# MainPower.net
KiCad netlist of a schematic drawn in Altium Designer
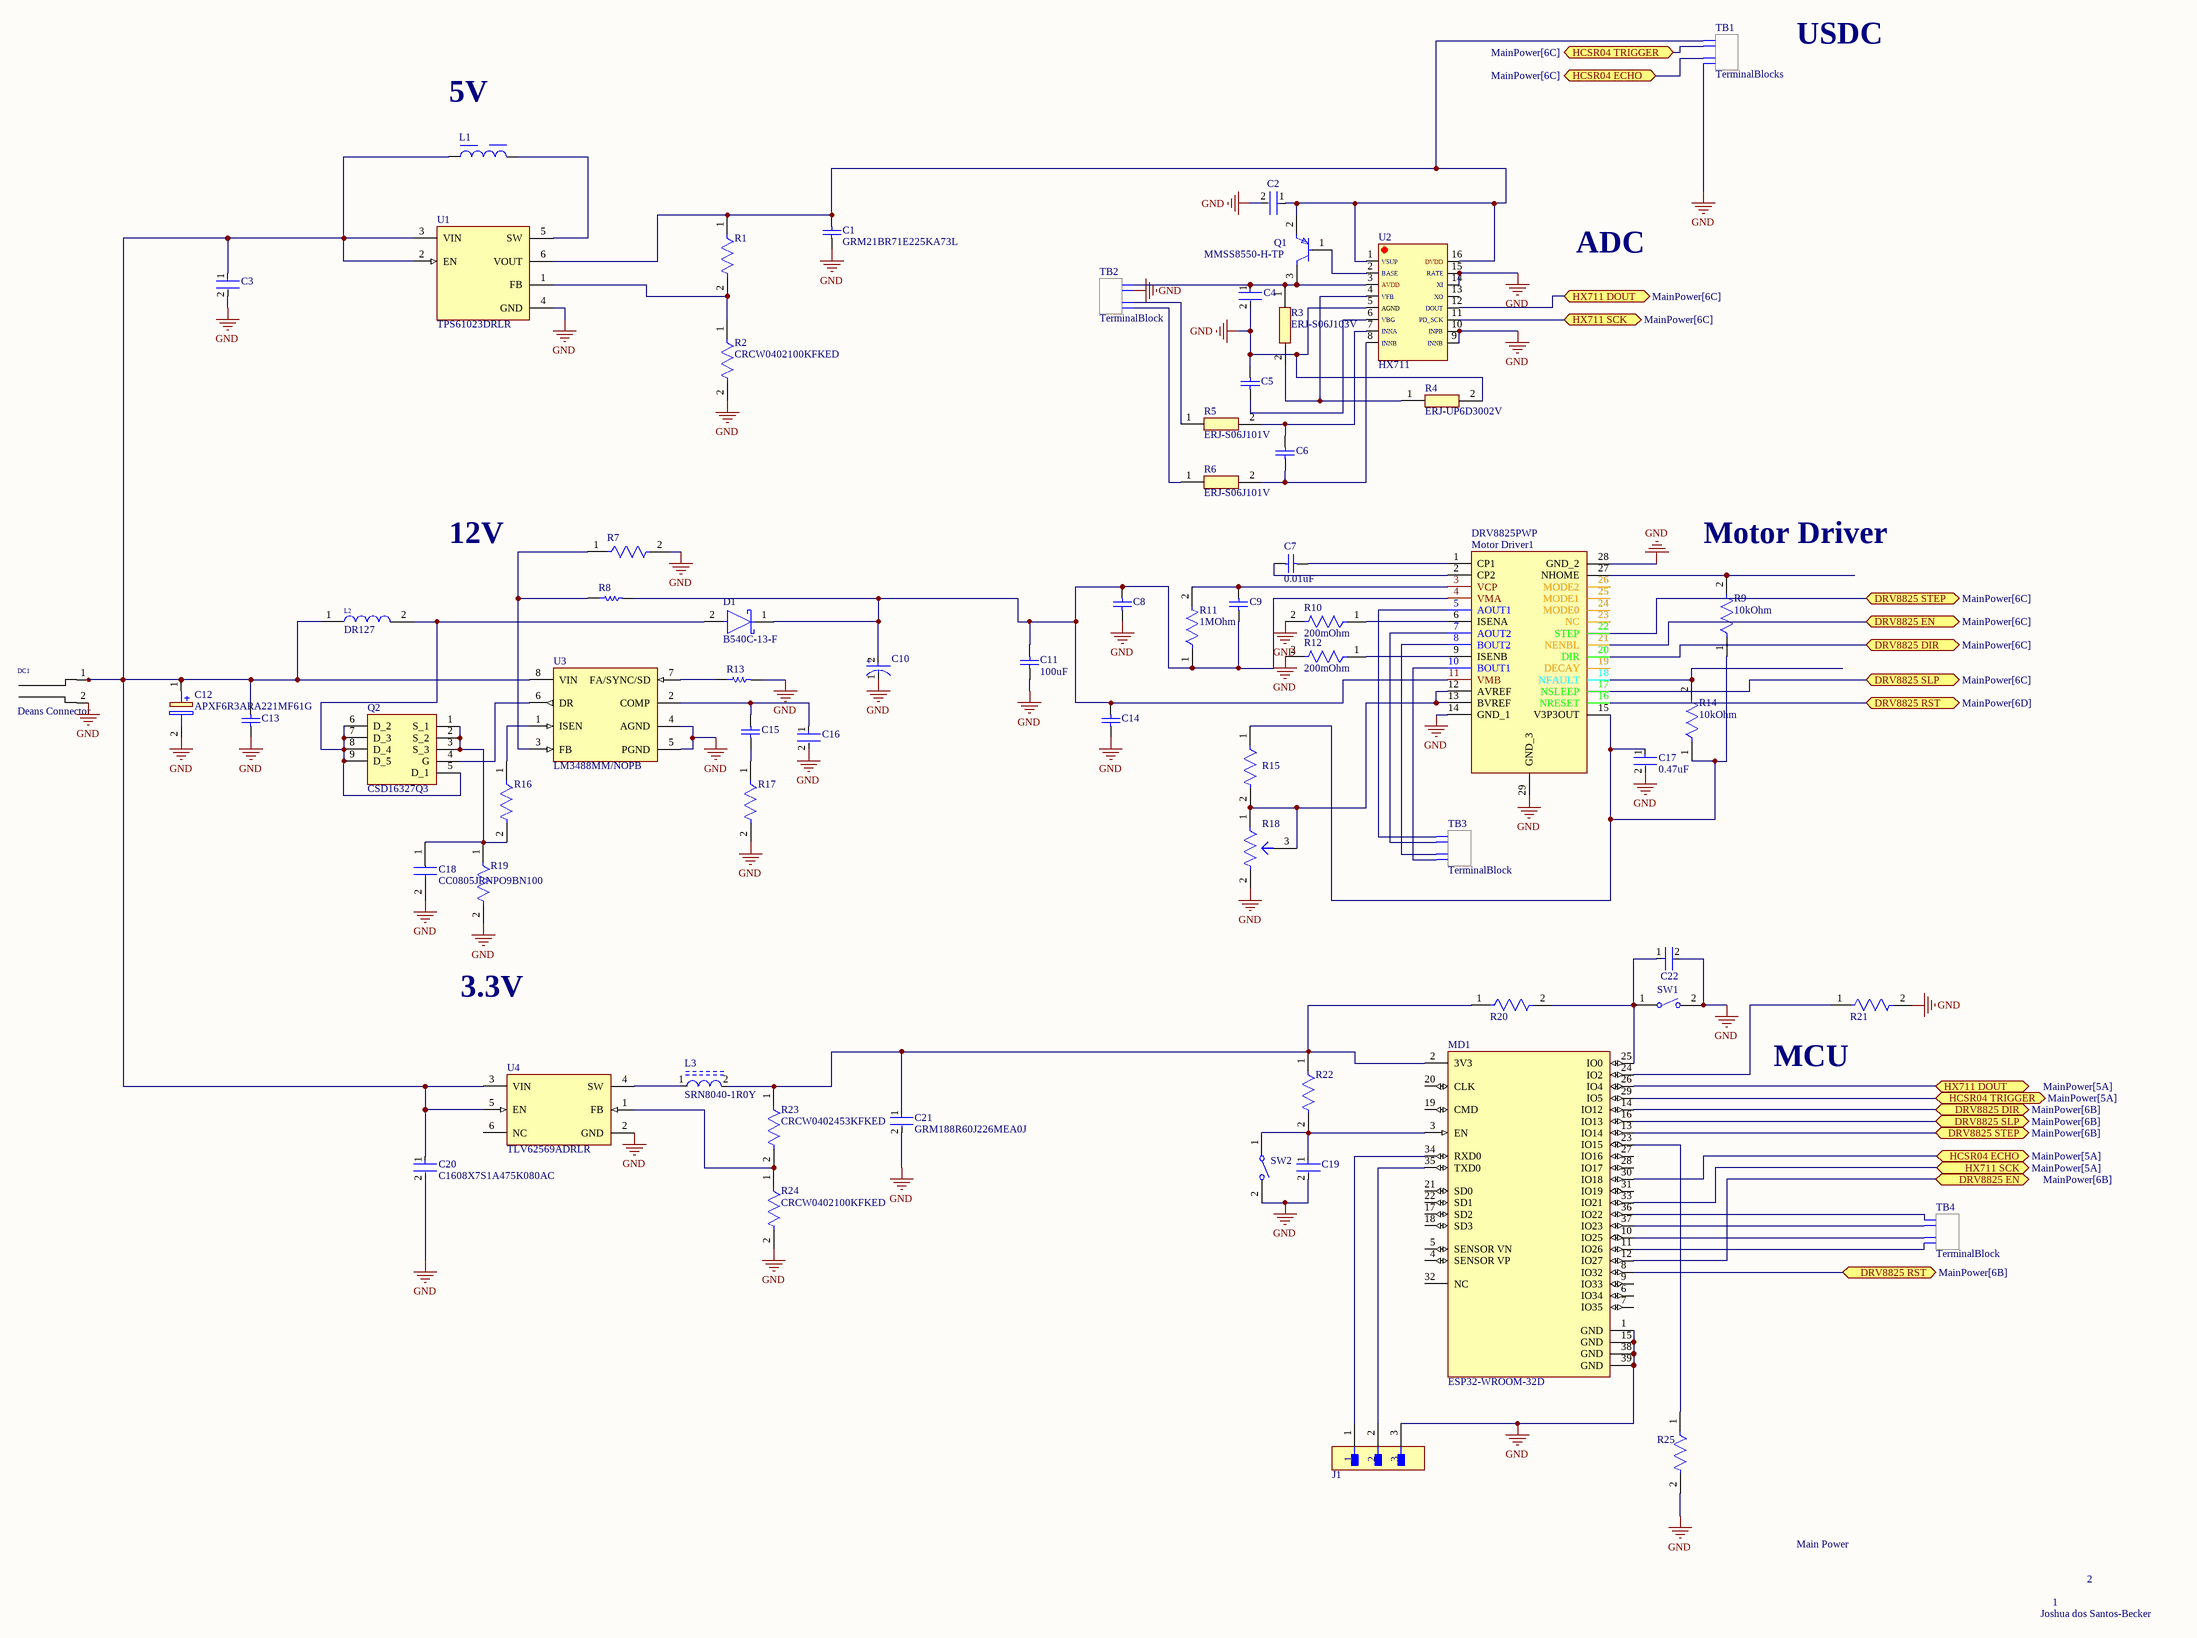
[diagram p0: MainPower.SchDoc]

(export (version "E")
  (design (tool "Eeschema 10.0.6"))
  (components
    (comp (ref "C1")
      (value "GRM21BR71E225KA73L")
      (footprint "CAPC2013X140X45NL15T25")
      (fields (field (name "MANUFACTURER") "Murata"))
      (libsource (lib "Altium Content Vault") (part "CAP"))
    )
    (comp (ref "C2")
      (value "GRM21BR61C106KE15L")
      (footprint "FP-GRM21B-0_1-IPC_C")
      (description "Chip Multilayer Ceramic Capacitors for General Purpose, 0805, 10uF, X5R, 15%, 10%, 16V")
      (fields (field (name "TOLERANCE") "10%") (field (name "VOLTAGE") "16V"))
      (libsource (lib "Altium Content Vault") (part "b4654b650e69147ec39a6b967a45e02"))
    )
    (comp (ref "C3")
      (value "C0805C106K8PACTU")
      (footprint "FP-C0805C-DG-MFG")
      (description "CAP CER 10UF 10V X5R 0805")
      (fields (field (name "TOLERANCE") "10%") (field (name "MANUFACTURER") "Kemet"))
      (libsource (lib "Altium Content Vault") (part "11868f565c42a9108669ba33697ecf6"))
    )
    (comp (ref "C4")
      (value "GRM21BR61C106KE15L")
      (footprint "FP-GRM21B-0_1-IPC_C")
      (description "Chip Multilayer Ceramic Capacitors for General Purpose, 0805, 10uF, X5R, 15%, 10%, 16V")
      (fields (field (name "TOLERANCE") "10%") (field (name "VOLTAGE") "16V"))
      (libsource (lib "Altium Content Vault") (part "b4654b650e69147ec39a6b967a45e02"))
    )
    (comp (ref "C5")
      (value "GRM033C71C104KE14J")
      (footprint "CAPC0603X33N")
      (fields (field (name "MOUSER PART NUMBER") "81-GRM033C71C104KE4J"))
      (libsource (lib "gsl") (part "0.1uF"))
    )
    (comp (ref "C6")
      (value "GRM033C71C104KE14J")
      (footprint "CAPC0603X33N")
      (fields (field (name "MOUSER PART NUMBER") "81-GRM033C71C104KE4J"))
      (libsource (lib "gsl") (part "0.1uF"))
    )
    (comp (ref "C7")
      (value "0.01uF")
      (footprint "FP-C0603-030-0_03-IPC_A")
      (description "C0603X5R1C103M030BA")
      (fields (field (name "TOLERANCE") "20%"))
      (libsource (lib "gsl") (part "0.01uF"))
    )
    (comp (ref "C8")
      (value "GRM033C71C104KE14J")
      (footprint "CAPC0603X33N")
      (fields (field (name "MOUSER PART NUMBER") "81-GRM033C71C104KE4J"))
      (libsource (lib "gsl") (part "0.1uF"))
    )
    (comp (ref "C9")
      (value "GRM033C71C104KE14J")
      (footprint "CAPC0603X33N")
      (fields (field (name "MOUSER PART NUMBER") "81-GRM033C71C104KE4J"))
      (libsource (lib "gsl") (part "0.1uF"))
    )
    (comp (ref "C10")
      (value "20SVPF390M")
      (footprint "FP-OS-CON-SMT-E12-MFG")
      (description "Conductive Polymer Aluminum Solid Capacitors (OS-CON) 390uF ±20% 20V")
      (fields (field (name "VOLTAGE") "20V") (field (name "TOLERANCE") "20%"))
      (libsource (lib "Altium Content Vault") (part "a00bbbee19879c290e62620ae7e47b1"))
    )
    (comp (ref "C11")
      (value "100uF")
      (footprint "CAPC3225X279N")
      (description "1210YD107MAT2A")
      (libsource (lib "gsl") (part "100uF"))
    )
    (comp (ref "C12")
      (value "APXF6R3ARA221MF61G")
      (footprint "SamacSys:CAPAE660X610N")
      (description "Capacitor Polarised")
      (fields (field (name "MOUSER PART NUMBER") "661-APXF6R3RA221MF61"))
      (libsource (lib "*") (part "APXF6R3ARA221MF61G"))
    )
    (comp (ref "C13")
      (value "GRM155R70J104KA01D")
      (footprint "CAPC1005X55X25NL05T10")
      (fields (field (name "MANUFACTURER") "Murata"))
      (libsource (lib "Altium Content Vault") (part "CAP"))
    )
    (comp (ref "C14")
      (value "GRM033C71C104KE14J")
      (footprint "CAPC0603X33N")
      (fields (field (name "MOUSER PART NUMBER") "81-GRM033C71C104KE4J"))
      (libsource (lib "gsl") (part "0.1uF"))
    )
    (comp (ref "C15")
      (value "GRM155R71C183KA01D")
      (footprint "CAPC1005X55X25NL05T10")
      (fields (field (name "MANUFACTURER") "Murata"))
      (libsource (lib "Altium Content Vault") (part "CAP"))
    )
    (comp (ref "C16")
      (value "CC0805KRX7R9BB102")
      (footprint "FP-CC0805-0_85-MFG")
      (description "CAP CER 1000PF 50V X7R 0805")
      (fields
        (field (name "MANUFACTURER") "Yageo")
        (field (name "OCTOPART") "https://octopart.com/cc0805krx7r9bb102-yageo-39467744")
      )
      (libsource (lib "Altium Content Vault") (part "11868f565c42a9108669ba33697ecf6"))
    )
    (comp (ref "C17")
      (value "0.47uF")
      (footprint "FP-1206-L_3_2_0_2-W_1_6_0-MFG")
      (description "12065C474K4Z2A")
      (fields (field (name "TOLERANCE") "10%"))
      (libsource (lib "Altium Content Vault") (part "b4654b650e69147ec39a6b967a45e02"))
    )
    (comp (ref "C18")
      (value "CC0805JRNPO9BN100")
      (footprint "SamacSys:CAPC2012X70N")
      (description "Capacitor")
      (fields (field (name "MOUSER PART NUMBER") "603-CC805JRNPO9BN100"))
      (libsource (lib "*") (part "CC0805JRNPO9BN100"))
    )
    (comp (ref "C19")
      (value "08055C104J4T2A")
      (footprint "FP-0805-L_2_01_0_2-W_1_25-MFG")
      (description "Automotive Ceramic Capacitor, 0805, 100nF, 5%, X7R, 15%, 50V")
      (fields (field (name "TOLERANCE") "5%"))
      (libsource (lib "Altium Content Vault") (part "02cd4be3c70576c341d710602a673aa"))
    )
    (comp (ref "C20")
      (value "C1608X7S1A475K080AC")
      (footprint "FP-C1608-080-MFG")
      (description "CAP CER 4.7UF 10V X7S 0603")
      (fields (field (name "TOLERANCE") "10%"))
      (libsource (lib "Altium Content Vault") (part "b4654b650e69147ec39a6b967a45e02"))
    )
    (comp (ref "C21")
      (value "GRM188R60J226MEA0J")
      (footprint "FP-GRM188-0_2-IPC_C")
      (description "Chip Multilayer Ceramic Capacitors for General Purpose, 0603, 22uF, X5R, 15%, 20%, 6.3V")
      (fields (field (name "TOLERANCE") "20%"))
      (libsource (lib "Altium Content Vault") (part "11868f565c42a9108669ba33697ecf6"))
    )
    (comp (ref "C22")
      (value "08055C104J4T2A")
      (footprint "FP-0805-L_2_01_0_2-W_1_25-MFG")
      (description "Automotive Ceramic Capacitor, 0805, 100nF, 5%, X7R, 15%, 50V")
      (fields (field (name "TOLERANCE") "5%"))
      (libsource (lib "Altium Content Vault") (part "02cd4be3c70576c341d710602a673aa"))
    )
    (comp (ref "D1")
      (value "B540C-13-F")
      (footprint "FP-SMC-MFG")
      (description "DIODE SCHOTTKY 40V 5A SMC")
      (fields
        (field (name "OCTOPART") "https://octopart.com/b540c-13-f-diodes+inc.-325873")
        (field (name "MANUFACTURER") "Diodes Inc.")
      )
      (libsource (lib "Altium Content Vault") (part "1d6ec82d83fb6aee721767c19dac4b9"))
    )
    (comp (ref "DC1")
      (value "Deans Connector")
      (footprint "Deans")
      (libsource (lib "gsl") (part "Deans Connector"))
    )
    (comp (ref "J1")
      (value "PREC003SAAN-RC")
      (footprint "FP-PREC003SAAN-RC-MFG")
      (description "PREC003SAAN-RC Conn Header Vert 3POS 2.54MM")
      (libsource (lib "Altium Content Vault") (part "0d3f023dd272f625e17a2be33dea85f"))
    )
    (comp (ref "L1")
      (value "74404043010A")
      (footprint "WE-LQS_4025")
      (description "74404043010A WE-LQS SMT Semi-Shielded Power Inductor")
      (libsource (lib "Altium Content Vault") (part "Inductor - 3"))
    )
    (comp (ref "L2") (value "DR127") (footprint "DR127") (libsource (lib "gsl") (part "DR127")))
    (comp (ref "L3")
      (value "SRN8040-1R0Y")
      (footprint "FP-SRN8040-MFG")
      (description "FIXED IND 1UH 7.8A 10 MOHM SMD")
      (fields (field (name "TOLERANCE") "30%"))
      (libsource (lib "Altium Content Vault") (part "faee11374f111f4f771645e57fa9eac"))
    )
    (comp (ref "MD1")
      (value "ESP32-WROOM-32D")
      (footprint "ESP32-WROOM-32D")
      (description "RX TXRX MOD WIFI SURFACE MOUNT")
      (libsource (lib "gsl") (part "ee866abf0b6c51247b7f5cdebf2f250"))
    )
    (comp (ref "Motor Driver1")
      (value "DRV8825PWP")
      (footprint "SOP65P640X120-29N")
      (fields (field (name "MOUSER PART NUMBER") "595-DRV8825PWP"))
      (libsource (lib "gsl") (part "DRV8825PWP"))
    )
    (comp (ref "Q1")
      (value "MMSS8550-H-TP")
      (footprint "FP-SOT-23-IPC_B")
      (description "TRANS PNP 25V 1.5A SOT23")
      (libsource (lib "Altium Content Vault") (part "0e8486ed3b47d9c69b8404ba87cf0f7"))
    )
    (comp (ref "Q2")
      (value "CSD16327Q3")
      (footprint "SamacSys:CSD16327Q3")
      (description "MOSFET (N-Channel)")
      (fields (field (name "MOUSER PART NUMBER") "595-CSD16327Q3"))
      (libsource (lib "*") (part "CSD16327Q3"))
    )
    (comp (ref "R1")
      (value "RC0603FR-07732KL")
      (footprint "FP-RC0603-0_55-IPC_A")
      (description "RES SMD 732K OHM 1% 1/10W 0603")
      (fields (field (name "TOLERANCE") "1%"))
      (libsource (lib "Altium Content Vault") (part "1029c3af85768c4190bb7ad29bc67b5"))
    )
    (comp (ref "R2")
      (value "CRCW0402100KFKED")
      (footprint "FP-CRCW0402-e3-IPC_C")
      (description "RES Thick Film, 100kΩ, 1%, 0.063W, 100ppm/°C, 0402")
      (fields (field (name "TOLERANCE") "1%"))
      (libsource (lib "Altium Content Vault") (part "1029c3af85768c4190bb7ad29bc67b5"))
    )
    (comp (ref "R3")
      (value "ERJ-S06J103V")
      (footprint "SamacSys:RESC2012X70N")
      (description "Resistor")
      (fields (field (name "MOUSER PART NUMBER") "667-ERJ-S06J103V"))
      (libsource (lib "*") (part "ERJ-S06J103V"))
    )
    (comp (ref "R4")
      (value "ERJ-UP6D3002V")
      (footprint "SamacSys:ERJUP6")
      (description "Resistor")
      (libsource (lib "*") (part "ERJ-UP6D3002V"))
    )
    (comp (ref "R5")
      (value "ERJ-S06J101V")
      (footprint "SamacSys:RESC2012X70N")
      (description "Resistor")
      (fields (field (name "MOUSER PART NUMBER") "667-ERJ-S06J101V"))
      (libsource (lib "*") (part "ERJ-S06J101V"))
    )
    (comp (ref "R6")
      (value "ERJ-S06J101V")
      (footprint "SamacSys:RESC2012X70N")
      (description "Resistor")
      (fields (field (name "MOUSER PART NUMBER") "667-ERJ-S06J101V"))
      (libsource (lib "*") (part "ERJ-S06J101V"))
    )
    (comp (ref "R7")
      (value "CRCW04021K00FKED")
      (footprint "FP-CRCW0402-e3-MFG")
      (description "RES Thick Film, 1kΩ, 1%, 0.063W, 100ppm/°C, 0402")
      (fields (field (name "TOLERANCE") "1%"))
      (libsource (lib "Altium Content Vault") (part "1029c3af85768c4190bb7ad29bc67b5"))
    )
    (comp (ref "R8")
      (value "CRCW04028K45FKED")
      (footprint "RESC1005X40X25LL05T05")
      (fields (field (name "MANUFACTURER") "Vishay Dale"))
      (libsource (lib "Altium Content Vault") (part "RES"))
    )
    (comp (ref "R9")
      (value "10kOhm")
      (footprint "FP-ESR10-IPC_C")
      (description "ESR10EZPD1002")
      (libsource (lib "Altium Content Vault") (part "1029c3af85768c4190bb7ad29bc67b5"))
    )
    (comp (ref "R10")
      (value "200mOhm")
      (footprint "WSL2512R2000FEA")
      (description "WSL2512R2000FEA")
      (libsource (lib "gsl") (part "200mOhm"))
    )
    (comp (ref "R11")
      (value "1MOhm")
      (footprint "RESC1005X40N")
      (description "CRCW04021M00FKEDHP")
      (libsource (lib "gsl") (part "1MOhm"))
    )
    (comp (ref "R12")
      (value "200mOhm")
      (footprint "WSL2512R2000FEA")
      (description "WSL2512R2000FEA")
      (libsource (lib "gsl") (part "200mOhm"))
    )
    (comp (ref "R13")
      (value "CRCW040226K1FKED")
      (footprint "RESC1005X40X25LL05T05")
      (fields (field (name "MANUFACTURER") "Vishay Dale"))
      (libsource (lib "Altium Content Vault") (part "RES"))
    )
    (comp (ref "R14")
      (value "10kOhm")
      (footprint "FP-ESR10-IPC_C")
      (description "ESR10EZPD1002")
      (libsource (lib "Altium Content Vault") (part "1029c3af85768c4190bb7ad29bc67b5"))
    )
    (comp (ref "R15")
      (value "~")
      (footprint "RESC1005X40N")
      (description "CRCW040250K0FKED")
      (libsource (lib "gsl") (part "50kOhm"))
    )
    (comp (ref "R16")
      (value "CRCW0402100RFKED")
      (footprint "FP-CRCW0402-e3-IPC_C")
      (description "RES Thick Film, 100Ω, 1%, 0.063W, 100ppm/°C, 0402")
      (fields (field (name "TOLERANCE") "1%"))
      (libsource (lib "Altium Content Vault") (part "1029c3af85768c4190bb7ad29bc67b5"))
    )
    (comp (ref "R17")
      (value "CRCW04025K11FKED")
      (footprint "FP-CRCW0402-e3-IPC_C")
      (description "RES Thick Film, 5.11kΩ, 1%, 0.063W, 100ppm/°C, 0402")
      (fields (field (name "TOLERANCE") "1%"))
      (libsource (lib "Altium Content Vault") (part "1029c3af85768c4190bb7ad29bc67b5"))
    )
    (comp (ref "R18")
      (value "~")
      (footprint "SMD Pot")
      (description "TC33X-2-303E Bourns")
      (libsource (lib "gsl") (part "30kPot"))
    )
    (comp (ref "R19")
      (value "PRL1632-R006-F-T1")
      (footprint "FP-PRL1632-MFG")
      (description "6 mOhms ±1% 1W Chip Resistor Wide 0612 (1632 Metric), Current Sense Thin Film")
      (fields (field (name "TOLERANCE") "1%"))
      (libsource (lib "Altium Content Vault") (part "1029c3af85768c4190bb7ad29bc67b5"))
    )
    (comp (ref "R20")
      (value "ESR10EZPD1002")
      (footprint "FP-ESR10-IPC_C")
      (description "10kΩ ±0.5% 0.4W 0805 Anti-Surge Chip Resistor AEC-Q200")
      (libsource (lib "Altium Content Vault") (part "1029c3af85768c4190bb7ad29bc67b5"))
    )
    (comp (ref "R21")
      (value "ESR10EZPD1002")
      (footprint "FP-ESR10-IPC_C")
      (description "10kΩ ±0.5% 0.4W 0805 Anti-Surge Chip Resistor AEC-Q200")
      (libsource (lib "Altium Content Vault") (part "1029c3af85768c4190bb7ad29bc67b5"))
    )
    (comp (ref "R22")
      (value "ESR10EZPD1002")
      (footprint "FP-ESR10-IPC_C")
      (description "10kΩ ±0.5% 0.4W 0805 Anti-Surge Chip Resistor AEC-Q200")
      (libsource (lib "Altium Content Vault") (part "1029c3af85768c4190bb7ad29bc67b5"))
    )
    (comp (ref "R23")
      (value "CRCW0402453KFKED")
      (footprint "FP-CRCW0402-e3-MFG")
      (description "RES Thick Film, 453kΩ, 1%, 0.063W, 100ppm/°C, 0402")
      (fields (field (name "TOLERANCE") "1%"))
      (libsource (lib "Altium Content Vault") (part "1029c3af85768c4190bb7ad29bc67b5"))
    )
    (comp (ref "R24")
      (value "CRCW0402100KFKED")
      (footprint "FP-CRCW0402-e3-IPC_C")
      (description "RES Thick Film, 100kΩ, 1%, 0.063W, 100ppm/°C, 0402")
      (fields (field (name "TOLERANCE") "1%"))
      (libsource (lib "Altium Content Vault") (part "1029c3af85768c4190bb7ad29bc67b5"))
    )
    (comp (ref "R25")
      (value "ESR10EZPD1002")
      (footprint "FP-ESR10-IPC_C")
      (description "10kΩ ±0.5% 0.4W 0805 Anti-Surge Chip Resistor AEC-Q200")
      (libsource (lib "Altium Content Vault") (part "1029c3af85768c4190bb7ad29bc67b5"))
    )
    (comp (ref "SW1")
      (value "FSMSM")
      (footprint "TECO-FSMSM-2_V")
      (description "FSMSM Push Button Switch, 50 mA, -35 to 85 degC, 2-Pin SMD, RoHS, Bulk")
      (fields (field (name "MANUFACTURER") "TE Connectivity"))
      (libsource (lib "Altium Content Vault") (part "SW-SPST-2_C"))
    )
    (comp (ref "SW2")
      (value "FSMSM")
      (footprint "TECO-FSMSM-2_V")
      (description "FSMSM Push Button Switch, 50 mA, -35 to 85 degC, 2-Pin SMD, RoHS, Bulk")
      (fields (field (name "MANUFACTURER") "TE Connectivity"))
      (libsource (lib "Altium Content Vault") (part "SW-SPST-2_C"))
    )
    (comp (ref "TB1")
      (value "TerminalBlocks")
      (footprint "PHOENIX_1725672")
      (libsource (lib "") (part "TerminalBlock_1"))
    )
    (comp (ref "TB2")
      (value "TerminalBlock")
      (footprint "PHOENIX_1725672")
      (libsource (lib "gsl") (part "TerminalBlock"))
    )
    (comp (ref "TB3")
      (value "TerminalBlock")
      (footprint "PHOENIX_1725672")
      (libsource (lib "") (part "TerminalBlock_1"))
    )
    (comp (ref "TB4")
      (value "TerminalBlock")
      (footprint "PHOENIX_1725672")
      (libsource (lib "") (part "TerminalBlock_1"))
    )
    (comp (ref "U1")
      (value "TPS61023DRLR")
      (footprint "FP-DRL0006A-MFG")
      (description "FINISH GOODS FOR TPS61023")
      (libsource (lib "Altium Content Vault") (part "b28b3e956a4ad07201ce69f9d09f9a8"))
    )
    (comp (ref "U2") (value "HX711") (footprint "TSOP127P600X160-16N") (libsource (lib "gsl") (part "HX711")))
    (comp (ref "U3")
      (value "LM3488MM/NOPB")
      (footprint "DGK0008A_M")
      (fields (field (name "MANUFACTURER") "Texas Instruments"))
      (libsource (lib "Altium Content Vault") (part "PM-SWREG-LM3488-8"))
    )
    (comp (ref "U4")
      (value "TLV62569ADRLR")
      (footprint "FP-DRL0006A-MFG")
      (description "IC REG BUCK ADJ 2A SOT563")
      (libsource (lib "Altium Content Vault") (part "c065b8f3016c1e0e14a773cb518fcf3"))
    )
  )
  (nets
    (net (code "1") (name "/DRV8825 DIR") (class "Default")
      (node (ref "MD1") (pin "14") (pinfunction "IO12_14") (pintype "bidirectional"))
      (node (ref "Motor Driver1") (pin "20") (pinfunction "DIR_20") (pintype "passive"))
    )
    (net (code "2") (name "/DRV8825 EN") (class "Default")
      (node (ref "MD1") (pin "12") (pinfunction "IO27_12") (pintype "bidirectional"))
      (node (ref "Motor Driver1") (pin "21") (pinfunction "NENBL_21") (pintype "passive"))
    )
    (net (code "3") (name "/DRV8825 RST") (class "Default")
      (node (ref "MD1") (pin "8") (pinfunction "IO32_8") (pintype "bidirectional"))
      (node (ref "Motor Driver1") (pin "16") (pinfunction "NRESET_16") (pintype "passive"))
    )
    (net (code "4") (name "/DRV8825 SLP") (class "Default")
      (node (ref "MD1") (pin "16") (pinfunction "IO13_16") (pintype "bidirectional"))
      (node (ref "Motor Driver1") (pin "17") (pinfunction "NSLEEP_17") (pintype "passive"))
    )
    (net (code "5") (name "/DRV8825 STEP") (class "Default")
      (node (ref "MD1") (pin "13") (pinfunction "IO14_13") (pintype "bidirectional"))
      (node (ref "Motor Driver1") (pin "22") (pinfunction "STEP_22") (pintype "passive"))
    )
    (net (code "6") (name "/HCSR04 ECHO") (class "Default")
      (node (ref "MD1") (pin "30") (pinfunction "IO18_30") (pintype "bidirectional"))
      (node (ref "TB1") (pin "3") (pinfunction "3_3") (pintype "passive"))
    )
    (net (code "7") (name "/HCSR04 TRIGGER") (class "Default")
      (node (ref "MD1") (pin "29") (pinfunction "IO5_29") (pintype "bidirectional"))
      (node (ref "TB1") (pin "2") (pinfunction "2_2") (pintype "passive"))
    )
    (net (code "8") (name "/HX711 DOUT") (class "Default")
      (node (ref "MD1") (pin "26") (pinfunction "IO4_26") (pintype "bidirectional"))
      (node (ref "U2") (pin "12") (pinfunction "12_12") (pintype "passive"))
    )
    (net (code "9") (name "/HX711 SCK") (class "Default")
      (node (ref "MD1") (pin "33") (pinfunction "IO21_33") (pintype "bidirectional"))
      (node (ref "U2") (pin "11") (pinfunction "11_11") (pintype "passive"))
    )
    (net (code "10") (name "GND") (class "Default")
      (node (ref "C1") (pin "2") (pinfunction "2_2") (pintype "passive"))
      (node (ref "C10") (pin "1") (pinfunction "C_1") (pintype "passive"))
      (node (ref "C11") (pin "1") (pinfunction "1_1") (pintype "passive"))
      (node (ref "C12") (pin "2") (pinfunction "-_2") (pintype "passive"))
      (node (ref "C13") (pin "2") (pinfunction "2_2") (pintype "passive"))
      (node (ref "C14") (pin "1") (pinfunction "1_1") (pintype "passive"))
      (node (ref "C16") (pin "2") (pinfunction "2_2") (pintype "passive"))
      (node (ref "C17") (pin "2") (pinfunction "2_2") (pintype "passive"))
      (node (ref "C18") (pin "2") (pinfunction "2_2") (pintype "passive"))
      (node (ref "C19") (pin "2") (pinfunction "2_2") (pintype "passive"))
      (node (ref "C2") (pin "2") (pinfunction "2_2") (pintype "passive"))
      (node (ref "C20") (pin "2") (pinfunction "2_2") (pintype "passive"))
      (node (ref "C21") (pin "2") (pinfunction "2_2") (pintype "passive"))
      (node (ref "C22") (pin "2") (pinfunction "2_2") (pintype "passive"))
      (node (ref "C3") (pin "2") (pinfunction "2_2") (pintype "passive"))
      (node (ref "C4") (pin "2") (pinfunction "2_2") (pintype "passive"))
      (node (ref "C5") (pin "2") (pinfunction "2_2") (pintype "passive"))
      (node (ref "C8") (pin "1") (pinfunction "1_1") (pintype "passive"))
      (node (ref "DC1") (pin "2") (pinfunction "2_2") (pintype "passive"))
      (node (ref "J1") (pin "3") (pinfunction "3_3") (pintype "passive"))
      (node (ref "MD1") (pin "1") (pinfunction "GND_1") (pintype "power_in"))
      (node (ref "MD1") (pin "15") (pinfunction "GND_15") (pintype "power_in"))
      (node (ref "MD1") (pin "38") (pinfunction "GND_38") (pintype "power_in"))
      (node (ref "MD1") (pin "39") (pinfunction "GND_39") (pintype "power_in"))
      (node (ref "Motor Driver1") (pin "14") (pinfunction "GND_1_14") (pintype "passive"))
      (node (ref "Motor Driver1") (pin "28") (pinfunction "GND_2_28") (pintype "passive"))
      (node (ref "Motor Driver1") (pin "29") (pinfunction "GND_3_29") (pintype "passive"))
      (node (ref "R10") (pin "2") (pinfunction "2_2") (pintype "passive"))
      (node (ref "R12") (pin "2") (pinfunction "2_2") (pintype "passive"))
      (node (ref "R13") (pin "2") (pinfunction "2_2") (pintype "passive"))
      (node (ref "R17") (pin "2") (pinfunction "2_2") (pintype "passive"))
      (node (ref "R18") (pin "2") (pinfunction "2_2") (pintype "passive"))
      (node (ref "R19") (pin "2") (pinfunction "2_2") (pintype "passive"))
      (node (ref "R2") (pin "2") (pinfunction "2_2") (pintype "passive"))
      (node (ref "R21") (pin "2") (pinfunction "2_2") (pintype "passive"))
      (node (ref "R24") (pin "2") (pinfunction "2_2") (pintype "passive"))
      (node (ref "R25") (pin "2") (pinfunction "2_2") (pintype "passive"))
      (node (ref "R4") (pin "2") (pinfunction "2_2") (pintype "passive"))
      (node (ref "R7") (pin "2") (pinfunction "2_2") (pintype "passive"))
      (node (ref "SW1") (pin "2") (pinfunction "2_2") (pintype "passive"))
      (node (ref "SW2") (pin "2") (pinfunction "2_2") (pintype "passive"))
      (node (ref "TB1") (pin "4") (pinfunction "4_4") (pintype "passive"))
      (node (ref "TB2") (pin "3") (pinfunction "3_3") (pintype "passive"))
      (node (ref "U1") (pin "4") (pinfunction "GND_4") (pintype "power_in"))
      (node (ref "U2") (pin "10") (pinfunction "10_10") (pintype "passive"))
      (node (ref "U2") (pin "14") (pinfunction "14_14") (pintype "passive"))
      (node (ref "U2") (pin "15") (pinfunction "15_15") (pintype "passive"))
      (node (ref "U2") (pin "5") (pinfunction "5_5") (pintype "passive"))
      (node (ref "U2") (pin "9") (pinfunction "9_9") (pintype "passive"))
      (node (ref "U3") (pin "4") (pinfunction "AGND_4") (pintype "power_in"))
      (node (ref "U3") (pin "5") (pinfunction "PGND_5") (pintype "power_in"))
      (node (ref "U4") (pin "2") (pinfunction "GND_2") (pintype "power_in"))
    )
    (net (code "11") (name "Net-(C5-Pad1)") (class "Default")
      (node (ref "C5") (pin "1") (pinfunction "1_1") (pintype "passive"))
      (node (ref "U2") (pin "6") (pinfunction "6_6") (pintype "passive"))
    )
    (net (code "12") (name "Net-(C6-Pad1)") (class "Default")
      (node (ref "C6") (pin "1") (pinfunction "1_1") (pintype "passive"))
      (node (ref "R6") (pin "2") (pinfunction "2_2") (pintype "passive"))
      (node (ref "U2") (pin "8") (pinfunction "8_8") (pintype "passive"))
    )
    (net (code "13") (name "Net-(C6-Pad2)") (class "Default")
      (node (ref "C6") (pin "2") (pinfunction "2_2") (pintype "passive"))
      (node (ref "R5") (pin "2") (pinfunction "2_2") (pintype "passive"))
      (node (ref "U2") (pin "7") (pinfunction "7_7") (pintype "passive"))
    )
    (net (code "14") (name "Net-(C10-A)") (class "Default")
      (node (ref "C10") (pin "2") (pinfunction "A_2") (pintype "passive"))
      (node (ref "C11") (pin "2") (pinfunction "2_2") (pintype "passive"))
      (node (ref "C14") (pin "2") (pinfunction "2_2") (pintype "passive"))
      (node (ref "C8") (pin "2") (pinfunction "2_2") (pintype "passive"))
      (node (ref "C9") (pin "1") (pinfunction "1_1") (pintype "passive"))
      (node (ref "D1") (pin "1") (pinfunction "C_1") (pintype "passive"))
      (node (ref "Motor Driver1") (pin "11") (pinfunction "VMB_11") (pintype "passive"))
      (node (ref "Motor Driver1") (pin "4") (pinfunction "VMA_4") (pintype "passive"))
      (node (ref "R11") (pin "1") (pinfunction "1_1") (pintype "passive"))
      (node (ref "R8") (pin "2") (pinfunction "2_2") (pintype "passive"))
    )
    (net (code "15") (name "Net-(C12-+)") (class "Default")
      (node (ref "C12") (pin "1") (pinfunction "+_1") (pintype "passive"))
      (node (ref "C13") (pin "1") (pinfunction "1_1") (pintype "passive"))
      (node (ref "C20") (pin "1") (pinfunction "1_1") (pintype "passive"))
      (node (ref "C3") (pin "1") (pinfunction "1_1") (pintype "passive"))
      (node (ref "DC1") (pin "1") (pinfunction "1_1") (pintype "passive"))
      (node (ref "L1") (pin "1") (pinfunction "1_1") (pintype "passive"))
      (node (ref "L2") (pin "1") (pinfunction "1_1") (pintype "passive"))
      (node (ref "U1") (pin "2") (pinfunction "EN_2") (pintype "input"))
      (node (ref "U1") (pin "3") (pinfunction "VIN_3") (pintype "power_in"))
      (node (ref "U3") (pin "8") (pinfunction "VIN_8") (pintype "power_in"))
      (node (ref "U4") (pin "3") (pinfunction "VIN_3") (pintype "power_in"))
      (node (ref "U4") (pin "5") (pinfunction "EN_5") (pintype "input"))
    )
    (net (code "16") (name "Net-(C15-Pad2)") (class "Default")
      (node (ref "C15") (pin "2") (pinfunction "2_2") (pintype "passive"))
      (node (ref "R17") (pin "1") (pinfunction "1_1") (pintype "passive"))
    )
    (net (code "17") (name "Net-(D1-A)") (class "Default")
      (node (ref "D1") (pin "2") (pinfunction "A_2") (pintype "passive"))
      (node (ref "L2") (pin "2") (pinfunction "2_2") (pintype "passive"))
      (node (ref "Q2") (pin "5") (pinfunction "D_1_5") (pintype "passive"))
      (node (ref "Q2") (pin "6") (pinfunction "D_2_6") (pintype "passive"))
      (node (ref "Q2") (pin "7") (pinfunction "D_3_7") (pintype "passive"))
      (node (ref "Q2") (pin "8") (pinfunction "D_4_8") (pintype "passive"))
      (node (ref "Q2") (pin "9") (pinfunction "D_5_9") (pintype "passive"))
    )
    (net (code "18") (name "Net-(MD1-3V3)") (class "Default")
      (node (ref "C21") (pin "1") (pinfunction "1_1") (pintype "passive"))
      (node (ref "L3") (pin "2") (pinfunction "2_2") (pintype "passive"))
      (node (ref "MD1") (pin "2") (pinfunction "3V3_2") (pintype "power_in"))
      (node (ref "R20") (pin "1") (pinfunction "1_1") (pintype "passive"))
      (node (ref "R22") (pin "1") (pinfunction "1_1") (pintype "passive"))
      (node (ref "R23") (pin "1") (pinfunction "1_1") (pintype "passive"))
    )
    (net (code "19") (name "Net-(MD1-EN)") (class "Default")
      (node (ref "C19") (pin "1") (pinfunction "1_1") (pintype "passive"))
      (node (ref "MD1") (pin "3") (pinfunction "EN_3") (pintype "input"))
      (node (ref "R22") (pin "2") (pinfunction "2_2") (pintype "passive"))
      (node (ref "SW2") (pin "1") (pinfunction "1_1") (pintype "passive"))
    )
    (net (code "20") (name "Net-(MD1-IO0)") (class "Default")
      (node (ref "C22") (pin "1") (pinfunction "1_1") (pintype "passive"))
      (node (ref "MD1") (pin "25") (pinfunction "IO0_25") (pintype "bidirectional"))
      (node (ref "R20") (pin "2") (pinfunction "2_2") (pintype "passive"))
      (node (ref "SW1") (pin "1") (pinfunction "1_1") (pintype "passive"))
    )
    (net (code "21") (name "Net-(MD1-IO2)") (class "Default")
      (node (ref "MD1") (pin "24") (pinfunction "IO2_24") (pintype "bidirectional"))
      (node (ref "R21") (pin "1") (pinfunction "1_1") (pintype "passive"))
    )
    (net (code "22") (name "Net-(MD1-IO15)") (class "Default")
      (node (ref "MD1") (pin "23") (pinfunction "IO15_23") (pintype "bidirectional"))
      (node (ref "R25") (pin "1") (pinfunction "1_1") (pintype "passive"))
    )
    (net (code "23") (name "Net-(MD1-IO22)") (class "Default")
      (node (ref "MD1") (pin "36") (pinfunction "IO22_36") (pintype "bidirectional"))
      (node (ref "TB4") (pin "1") (pinfunction "1_1") (pintype "passive"))
    )
    (net (code "24") (name "Net-(MD1-IO23)") (class "Default")
      (node (ref "MD1") (pin "37") (pinfunction "IO23_37") (pintype "bidirectional"))
      (node (ref "TB4") (pin "2") (pinfunction "2_2") (pintype "passive"))
    )
    (net (code "25") (name "Net-(MD1-IO25)") (class "Default")
      (node (ref "MD1") (pin "10") (pinfunction "IO25_10") (pintype "bidirectional"))
      (node (ref "TB4") (pin "3") (pinfunction "3_3") (pintype "passive"))
    )
    (net (code "26") (name "Net-(MD1-IO26)") (class "Default")
      (node (ref "MD1") (pin "11") (pinfunction "IO26_11") (pintype "bidirectional"))
      (node (ref "TB4") (pin "4") (pinfunction "4_4") (pintype "passive"))
    )
    (net (code "27") (name "Net-(MD1-RXD0)") (class "Default")
      (node (ref "J1") (pin "1") (pinfunction "1_1") (pintype "passive"))
      (node (ref "MD1") (pin "34") (pinfunction "RXD0_34") (pintype "bidirectional"))
    )
    (net (code "28") (name "Net-(MD1-TXD0)") (class "Default")
      (node (ref "J1") (pin "2") (pinfunction "2_2") (pintype "passive"))
      (node (ref "MD1") (pin "35") (pinfunction "TXD0_35") (pintype "bidirectional"))
    )
    (net (code "29") (name "Net-(Motor Driver1-AOUT1)") (class "Default")
      (node (ref "Motor Driver1") (pin "5") (pinfunction "AOUT1_5") (pintype "passive"))
      (node (ref "TB3") (pin "1") (pinfunction "1_1") (pintype "passive"))
    )
    (net (code "30") (name "Net-(Motor Driver1-AOUT2)") (class "Default")
      (node (ref "Motor Driver1") (pin "7") (pinfunction "AOUT2_7") (pintype "passive"))
      (node (ref "TB3") (pin "2") (pinfunction "2_2") (pintype "passive"))
    )
    (net (code "31") (name "Net-(Motor Driver1-AVREF)") (class "Default")
      (node (ref "Motor Driver1") (pin "12") (pinfunction "AVREF_12") (pintype "passive"))
      (node (ref "Motor Driver1") (pin "13") (pinfunction "BVREF_13") (pintype "passive"))
      (node (ref "R15") (pin "2") (pinfunction "2_2") (pintype "passive"))
      (node (ref "R18") (pin "1") (pinfunction "1_1") (pintype "passive"))
      (node (ref "R18") (pin "3") (pinfunction "3_3") (pintype "passive"))
    )
    (net (code "32") (name "Net-(Motor Driver1-BOUT1)") (class "Default")
      (node (ref "Motor Driver1") (pin "10") (pinfunction "BOUT1_10") (pintype "passive"))
      (node (ref "TB3") (pin "4") (pinfunction "4_4") (pintype "passive"))
    )
    (net (code "33") (name "Net-(Motor Driver1-BOUT2)") (class "Default")
      (node (ref "Motor Driver1") (pin "8") (pinfunction "BOUT2_8") (pintype "passive"))
      (node (ref "TB3") (pin "3") (pinfunction "3_3") (pintype "passive"))
    )
    (net (code "34") (name "Net-(Motor Driver1-CP1)") (class "Default")
      (node (ref "C7") (pin "1") (pinfunction "1_1") (pintype "passive"))
      (node (ref "Motor Driver1") (pin "1") (pinfunction "CP1_1") (pintype "passive"))
    )
    (net (code "35") (name "Net-(Motor Driver1-CP2)") (class "Default")
      (node (ref "C7") (pin "2") (pinfunction "2_2") (pintype "passive"))
      (node (ref "Motor Driver1") (pin "2") (pinfunction "CP2_2") (pintype "passive"))
    )
    (net (code "36") (name "Net-(Motor Driver1-ISENA)") (class "Default")
      (node (ref "Motor Driver1") (pin "6") (pinfunction "ISENA_6") (pintype "passive"))
      (node (ref "R10") (pin "1") (pinfunction "1_1") (pintype "passive"))
    )
    (net (code "37") (name "Net-(Motor Driver1-ISENB)") (class "Default")
      (node (ref "Motor Driver1") (pin "9") (pinfunction "ISENB_9") (pintype "passive"))
      (node (ref "R12") (pin "1") (pinfunction "1_1") (pintype "passive"))
    )
    (net (code "38") (name "Net-(Motor Driver1-NFAULT)") (class "Default")
      (node (ref "Motor Driver1") (pin "18") (pinfunction "NFAULT_18") (pintype "passive"))
      (node (ref "R14") (pin "2") (pinfunction "2_2") (pintype "passive"))
    )
    (net (code "39") (name "Net-(Motor Driver1-NHOME)") (class "Default")
      (node (ref "Motor Driver1") (pin "27") (pinfunction "NHOME_27") (pintype "passive"))
      (node (ref "R9") (pin "2") (pinfunction "2_2") (pintype "passive"))
    )
    (net (code "40") (name "Net-(Motor Driver1-V3P3OUT)") (class "Default")
      (node (ref "C17") (pin "1") (pinfunction "1_1") (pintype "passive"))
      (node (ref "Motor Driver1") (pin "15") (pinfunction "V3P3OUT_15") (pintype "passive"))
      (node (ref "R14") (pin "1") (pinfunction "1_1") (pintype "passive"))
      (node (ref "R15") (pin "1") (pinfunction "1_1") (pintype "passive"))
      (node (ref "R9") (pin "1") (pinfunction "1_1") (pintype "passive"))
    )
    (net (code "41") (name "Net-(Motor Driver1-VCP)") (class "Default")
      (node (ref "C9") (pin "2") (pinfunction "2_2") (pintype "passive"))
      (node (ref "Motor Driver1") (pin "3") (pinfunction "VCP_3") (pintype "passive"))
      (node (ref "R11") (pin "2") (pinfunction "2_2") (pintype "passive"))
    )
    (net (code "42") (name "Net-(Q1-B)") (class "Default")
      (node (ref "Q1") (pin "1") (pinfunction "B_1") (pintype "passive"))
      (node (ref "U2") (pin "2") (pinfunction "2_2") (pintype "passive"))
    )
    (net (code "43") (name "Net-(Q1-C)") (class "Default")
      (node (ref "C4") (pin "1") (pinfunction "1_1") (pintype "passive"))
      (node (ref "Q1") (pin "3") (pinfunction "C_3") (pintype "passive"))
      (node (ref "R3") (pin "1") (pinfunction "1_1") (pintype "passive"))
      (node (ref "TB2") (pin "4") (pinfunction "4_4") (pintype "passive"))
      (node (ref "U2") (pin "3") (pinfunction "3_3") (pintype "passive"))
    )
    (net (code "44") (name "Net-(Q1-E)") (class "Default")
      (node (ref "C1") (pin "1") (pinfunction "1_1") (pintype "passive"))
      (node (ref "C2") (pin "1") (pinfunction "1_1") (pintype "passive"))
      (node (ref "Q1") (pin "2") (pinfunction "E_2") (pintype "passive"))
      (node (ref "R1") (pin "1") (pinfunction "1_1") (pintype "passive"))
      (node (ref "TB1") (pin "1") (pinfunction "1_1") (pintype "passive"))
      (node (ref "U1") (pin "6") (pinfunction "VOUT_6") (pintype "power_in"))
      (node (ref "U2") (pin "1") (pinfunction "1_1") (pintype "passive"))
      (node (ref "U2") (pin "16") (pinfunction "16_16") (pintype "passive"))
    )
    (net (code "45") (name "Net-(Q2-G)") (class "Default")
      (node (ref "Q2") (pin "4") (pinfunction "G_4") (pintype "passive"))
      (node (ref "U3") (pin "6") (pinfunction "DR_6") (pintype "output"))
    )
    (net (code "46") (name "Net-(Q2-S_1)") (class "Default")
      (node (ref "C18") (pin "1") (pinfunction "1_1") (pintype "passive"))
      (node (ref "Q2") (pin "1") (pinfunction "S_1_1") (pintype "passive"))
      (node (ref "Q2") (pin "2") (pinfunction "S_2_2") (pintype "passive"))
      (node (ref "Q2") (pin "3") (pinfunction "S_3_3") (pintype "passive"))
      (node (ref "R16") (pin "2") (pinfunction "2_2") (pintype "passive"))
      (node (ref "R19") (pin "1") (pinfunction "1_1") (pintype "passive"))
    )
    (net (code "47") (name "Net-(R3-Pad2)") (class "Default")
      (node (ref "R3") (pin "2") (pinfunction "2_2") (pintype "passive"))
      (node (ref "R4") (pin "1") (pinfunction "1_1") (pintype "passive"))
      (node (ref "U2") (pin "4") (pinfunction "4_4") (pintype "passive"))
    )
    (net (code "48") (name "Net-(R5-Pad1)") (class "Default")
      (node (ref "R5") (pin "1") (pinfunction "1_1") (pintype "passive"))
      (node (ref "TB2") (pin "2") (pinfunction "2_2") (pintype "passive"))
    )
    (net (code "49") (name "Net-(R6-Pad1)") (class "Default")
      (node (ref "R6") (pin "1") (pinfunction "1_1") (pintype "passive"))
      (node (ref "TB2") (pin "1") (pinfunction "1_1") (pintype "passive"))
    )
    (net (code "50") (name "Net-(U1-FB)") (class "Default")
      (node (ref "R1") (pin "2") (pinfunction "2_2") (pintype "passive"))
      (node (ref "R2") (pin "1") (pinfunction "1_1") (pintype "passive"))
      (node (ref "U1") (pin "1") (pinfunction "FB_1") (pintype "passive"))
    )
    (net (code "51") (name "Net-(U1-SW)") (class "Default")
      (node (ref "L1") (pin "2") (pinfunction "2_2") (pintype "passive"))
      (node (ref "U1") (pin "5") (pinfunction "SW_5") (pintype "passive"))
    )
    (net (code "52") (name "Net-(U3-COMP)") (class "Default")
      (node (ref "C15") (pin "1") (pinfunction "1_1") (pintype "passive"))
      (node (ref "C16") (pin "1") (pinfunction "1_1") (pintype "passive"))
      (node (ref "U3") (pin "2") (pinfunction "COMP_2") (pintype "passive"))
    )
    (net (code "53") (name "Net-(U3-FA{slash}SYNC{slash}SD)") (class "Default")
      (node (ref "R13") (pin "1") (pinfunction "1_1") (pintype "passive"))
      (node (ref "U3") (pin "7") (pinfunction "FA/SYNC/SD_7") (pintype "input"))
    )
    (net (code "54") (name "Net-(U3-FB)") (class "Default")
      (node (ref "R7") (pin "1") (pinfunction "1_1") (pintype "passive"))
      (node (ref "R8") (pin "1") (pinfunction "1_1") (pintype "passive"))
      (node (ref "U3") (pin "3") (pinfunction "FB_3") (pintype "input"))
    )
    (net (code "55") (name "Net-(U3-ISEN)") (class "Default")
      (node (ref "R16") (pin "1") (pinfunction "1_1") (pintype "passive"))
      (node (ref "U3") (pin "1") (pinfunction "ISEN_1") (pintype "input"))
    )
    (net (code "56") (name "Net-(U4-FB)") (class "Default")
      (node (ref "R23") (pin "2") (pinfunction "2_2") (pintype "passive"))
      (node (ref "R24") (pin "1") (pinfunction "1_1") (pintype "passive"))
      (node (ref "U4") (pin "1") (pinfunction "FB_1") (pintype "input"))
    )
    (net (code "57") (name "Net-(U4-SW)") (class "Default")
      (node (ref "L3") (pin "1") (pinfunction "1_1") (pintype "passive"))
      (node (ref "U4") (pin "4") (pinfunction "SW_4") (pintype "passive"))
    )
    (net (code "58") (name "unconnected-(MD1-CLK-Pad20)") (class "Default")
      (node (ref "MD1") (pin "20") (pinfunction "CLK_20") (pintype "bidirectional"))
    )
    (net (code "59") (name "unconnected-(MD1-CMD-Pad19)") (class "Default")
      (node (ref "MD1") (pin "19") (pinfunction "CMD_19") (pintype "bidirectional"))
    )
    (net (code "60") (name "unconnected-(MD1-IO16-Pad27)") (class "Default")
      (node (ref "MD1") (pin "27") (pinfunction "IO16_27") (pintype "bidirectional"))
    )
    (net (code "61") (name "unconnected-(MD1-IO17-Pad28)") (class "Default")
      (node (ref "MD1") (pin "28") (pinfunction "IO17_28") (pintype "bidirectional"))
    )
    (net (code "62") (name "unconnected-(MD1-IO19-Pad31)") (class "Default")
      (node (ref "MD1") (pin "31") (pinfunction "IO19_31") (pintype "bidirectional"))
    )
    (net (code "63") (name "unconnected-(MD1-IO33-Pad9)") (class "Default")
      (node (ref "MD1") (pin "9") (pinfunction "IO33_9") (pintype "bidirectional"))
    )
    (net (code "64") (name "unconnected-(MD1-IO34-Pad6)") (class "Default")
      (node (ref "MD1") (pin "6") (pinfunction "IO34_6") (pintype "bidirectional"))
    )
    (net (code "65") (name "unconnected-(MD1-IO35-Pad7)") (class "Default")
      (node (ref "MD1") (pin "7") (pinfunction "IO35_7") (pintype "bidirectional"))
    )
    (net (code "66") (name "unconnected-(MD1-NC-Pad32)") (class "Default")
      (node (ref "MD1") (pin "32") (pinfunction "NC_32") (pintype "passive"))
    )
    (net (code "67") (name "unconnected-(MD1-SD0-Pad21)") (class "Default")
      (node (ref "MD1") (pin "21") (pinfunction "SD0_21") (pintype "bidirectional"))
    )
    (net (code "68") (name "unconnected-(MD1-SD1-Pad22)") (class "Default")
      (node (ref "MD1") (pin "22") (pinfunction "SD1_22") (pintype "bidirectional"))
    )
    (net (code "69") (name "unconnected-(MD1-SD2-Pad17)") (class "Default")
      (node (ref "MD1") (pin "17") (pinfunction "SD2_17") (pintype "bidirectional"))
    )
    (net (code "70") (name "unconnected-(MD1-SD3-Pad18)") (class "Default")
      (node (ref "MD1") (pin "18") (pinfunction "SD3_18") (pintype "bidirectional"))
    )
    (net (code "71") (name "unconnected-(MD1-SENSOR_VN-Pad5)") (class "Default")
      (node (ref "MD1") (pin "5") (pinfunction "SENSOR_VN_5") (pintype "bidirectional"))
    )
    (net (code "72") (name "unconnected-(MD1-SENSOR_VP-Pad4)") (class "Default")
      (node (ref "MD1") (pin "4") (pinfunction "SENSOR_VP_4") (pintype "bidirectional"))
    )
    (net (code "73") (name "unconnected-(Motor Driver1-DECAY-Pad19)") (class "Default")
      (node (ref "Motor Driver1") (pin "19") (pinfunction "DECAY_19") (pintype "passive"))
    )
    (net (code "74") (name "unconnected-(Motor Driver1-MODE0-Pad24)") (class "Default")
      (node (ref "Motor Driver1") (pin "24") (pinfunction "MODE0_24") (pintype "passive"))
    )
    (net (code "75") (name "unconnected-(Motor Driver1-MODE1-Pad25)") (class "Default")
      (node (ref "Motor Driver1") (pin "25") (pinfunction "MODE1_25") (pintype "passive"))
    )
    (net (code "76") (name "unconnected-(Motor Driver1-MODE2-Pad26)") (class "Default")
      (node (ref "Motor Driver1") (pin "26") (pinfunction "MODE2_26") (pintype "passive"))
    )
    (net (code "77") (name "unconnected-(Motor Driver1-NC-Pad23)") (class "Default")
      (node (ref "Motor Driver1") (pin "23") (pinfunction "NC_23") (pintype "passive"))
    )
    (net (code "78") (name "unconnected-(U2-Pad13)") (class "Default")
      (node (ref "U2") (pin "13") (pinfunction "13_13") (pintype "passive"))
    )
    (net (code "79") (name "unconnected-(U4-NC-Pad6)") (class "Default")
      (node (ref "U4") (pin "6") (pinfunction "NC_6") (pintype "passive"))
    )
  )
)
